# 08_-ALARM.net
KiCad netlist of a schematic drawn in Altium Designer
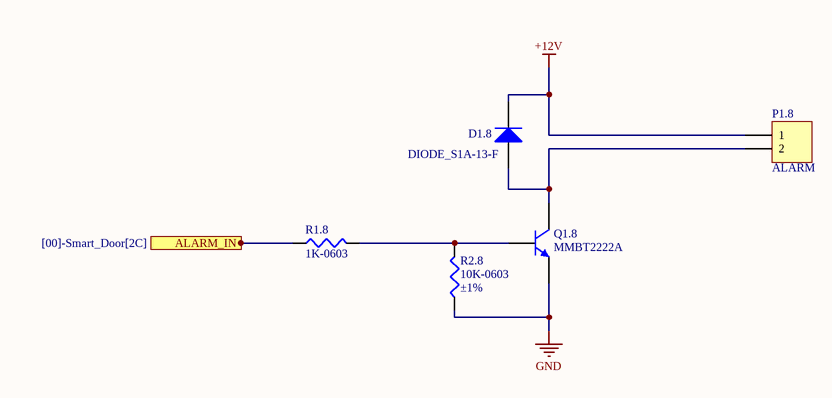
[diagram p0: [08]-ALARM.SchDoc]

(export (version "E")
  (design (tool "Eeschema 10.0.6"))
  (components
    (comp (ref "D1.8")
      (value "DIODE_S1A-13-F")
      (footprint "DO-214AC")
      (description "DIODE GEN PURP 50V 1A SMA")
      (fields
        (field (name "MANUFACTURER") "Diodes Incorporated")
        (field (name "MANUFACTURER PART NUMBER") "S1A-13-F")
      )
      (libsource (lib "Indruino") (part "DIODE_S1A-13-F"))
    )
    (comp (ref "P1.8")
      (value "ALARM")
      (footprint "MinhTien_PCBLib:DOMINO_2PIN_3.81MM_RUT")
      (libsource (lib "MinhTien_SCHLib") (part "Domino 2 pin"))
    )
    (comp (ref "Q1.8")
      (value "MMBT2222A")
      (footprint "Indruino:SOT23-3")
      (description "TRANS NPN 40V 1A SOT-23")
      (fields (field (name "MANUFACTURER") "ON Semiconductor") (field (name "BASE PART NUMBER") "MMBT2222"))
      (libsource (lib "Indruino") (part "MMBT2222A"))
    )
    (comp (ref "R1.8")
      (value "1K-0603")
      (footprint "RES0603")
      (description "RES SMD 1K OHM 5% 1/10W 0603")
      (fields (field (name "TOLERANCE") "±5%"))
      (libsource (lib "Indruino") (part "RC0603JR-071KL"))
    )
    (comp (ref "R2.8")
      (value "10K-0603")
      (footprint "RES0603")
      (description "RES SMD 10K OHM 1% 1/10W 0603")
      (fields
        (field (name "MANUFACTURER") "Yageo")
        (field (name "MANUFACTURER PART NUMBER") "RC0603FR-0710KL")
        (field (name "TOLERANCE") "±1%")
      )
      (libsource (lib "Indruino") (part "RC0603FR-0710KL"))
    )
  )
  (nets
    (net (code "1") (name "+12V") (class "Default")
      (node (ref "D1.8") (pin "2") (pinfunction "K_2") (pintype "passive"))
      (node (ref "P1.8") (pin "1") (pinfunction "1_1") (pintype "passive"))
    )
    (net (code "2") (name "/ALARM_IN") (class "Default")
      (node (ref "R1.8") (pin "1") (pinfunction "1_1") (pintype "passive"))
    )
    (net (code "3") (name "GND") (class "Default")
      (node (ref "Q1.8") (pin "2") (pinfunction "E_2") (pintype "passive"))
      (node (ref "R2.8") (pin "1") (pinfunction "1_1") (pintype "passive"))
    )
    (net (code "4") (name "Net-(D1.8-A)") (class "Default")
      (node (ref "D1.8") (pin "1") (pinfunction "A_1") (pintype "passive"))
      (node (ref "P1.8") (pin "2") (pinfunction "2_2") (pintype "passive"))
      (node (ref "Q1.8") (pin "3") (pinfunction "C_3") (pintype "passive"))
    )
    (net (code "5") (name "Net-(Q1.8-B)") (class "Default")
      (node (ref "Q1.8") (pin "1") (pinfunction "B_1") (pintype "passive"))
      (node (ref "R1.8") (pin "2") (pinfunction "2_2") (pintype "passive"))
      (node (ref "R2.8") (pin "2") (pinfunction "2_2") (pintype "passive"))
    )
  )
)
